# SCH-00001-AC-01.net
KiCad netlist of a schematic drawn in Altium Designer
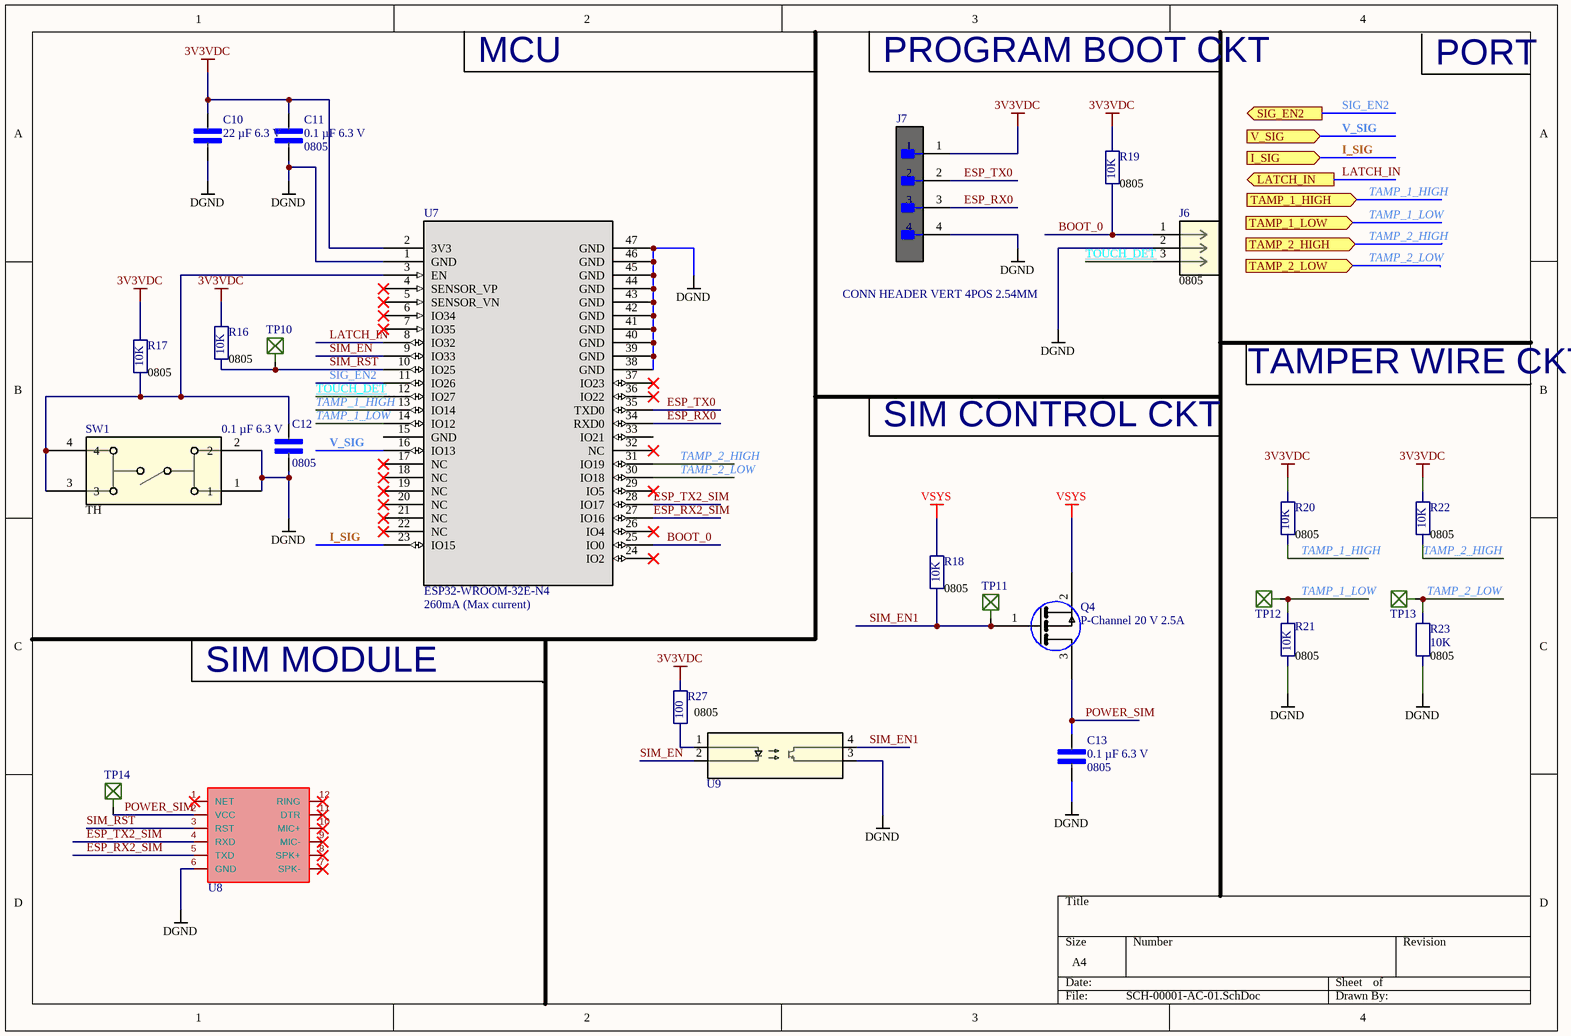
[diagram p0: SCH-00001-AC-01.SchDoc]

(export (version "E")
  (design (tool "Eeschema 10.0.6"))
  (components
    (comp (ref "C10")
      (value "22 µF 6.3 V")
      (footprint "CAP0805")
      (description "22 µF ±10% 6.3V Ceramic Capacitor X5R 0805 (2012 Metric)")
      (fields
        (field (name "MANUFACTURER") "Samsung Electro-Mechanics")
        (field (name "MANUFACTURER PART NO.") "CL21A226KQCLRNC")
        (field (name "DATE DRAWN") "03/9/2024")
        (field (name "DRAWN BY") "Varun Chakravarthy")
      )
      (libsource (lib "00001-A-01") (part "CL21A226KQCLRNC"))
    )
    (comp (ref "C11")
      (value "0.1 µF 6.3 V")
      (footprint "CAP0805")
      (description "0.1 µF ±10% 6.3V Ceramic Capacitor X5R 0805 (2012 Metric)")
      (fields
        (field (name "MANUFACTURER") "KYOCERA AVX")
        (field (name "MANUFACTURER PART NO.") "08056D104KAT2A")
        (field (name "VALUE 2") "0805")
        (field (name "DATE DRAWN") "04/07/24")
        (field (name "DRAWN BY") "Varun Chakravarthy")
      )
      (libsource (lib "00001-A-01") (part "08056D104KAT2A"))
    )
    (comp (ref "C12")
      (value "0.1 µF 6.3 V")
      (footprint "CAP0805")
      (description "0.1 µF ±10% 6.3V Ceramic Capacitor X5R 0805 (2012 Metric)")
      (fields
        (field (name "MANUFACTURER") "KYOCERA AVX")
        (field (name "MANUFACTURER PART NO.") "08056D104KAT2A")
        (field (name "VALUE 2") "0805")
        (field (name "DATE DRAWN") "04/07/24")
        (field (name "DRAWN BY") "Varun Chakravarthy")
      )
      (libsource (lib "00001-A-01") (part "08056D104KAT2A"))
    )
    (comp (ref "C13")
      (value "0.1 µF 6.3 V")
      (footprint "CAP0805")
      (description "0.1 µF ±10% 6.3V Ceramic Capacitor X5R 0805 (2012 Metric)")
      (fields
        (field (name "MANUFACTURER") "KYOCERA AVX")
        (field (name "MANUFACTURER PART NO.") "08056D104KAT2A")
        (field (name "VALUE 2") "0805")
        (field (name "DATE DRAWN") "04/07/24")
        (field (name "DRAWN BY") "Varun Chakravarthy")
      )
      (libsource (lib "00001-A-01") (part "08056D104KAT2A"))
    )
    (comp (ref "J6")
      (value "PRPC003SAAN-RC")
      (footprint "CONN_PRPC003SAAN-RC_SUL")
      (description "Connector Header Through Hole 3 position 0.100\" (2.54mm)")
      (fields
        (field (name "MANUFACTURER") "Sullins Connector Solutions")
        (field (name "DISTRIBUTOR 1 PART NO.") "S1011EC-03-ND")
        (field (name "PACKAGE") "0805")
        (field (name "DATE DRAWN") "12/9/2024")
        (field (name "VERIFIED BY") "*")
      )
      (libsource (lib "00001-A-01") (part "PRPC003SAAN-RC"))
    )
    (comp (ref "J7")
      (value "CONN HEADER VERT 4POS 2.54MM")
      (footprint "Amphenol_FCI_0_MFG")
      (description "Connector Header Through Hole 4 position 0.100\" (2.54mm)")
      (fields
        (field (name "MANUFACTURER") "Amphenol ICC (FCI)")
        (field (name "MANUFACTURER PART NO.") "68000-204HLF")
        (field (name "DATE DRAWN") "3/9/2024")
        (field (name "VERIFIED BY") "*")
      )
      (libsource (lib "00001-A-01") (part "68000-204HLF"))
    )
    (comp (ref "Q4")
      (value "P-Channel 20 V 2.5A")
      (footprint "SOT23_DMG2301U_DIO")
      (description "P-Channel 20 V 2.5A (Ta) 800mW (Ta) Surface Mount SOT-23-3")
      (fields
        (field (name "MANUFACTURER") "Diodes Incorporated")
        (field (name "MANUFACTURER PART NO.") "DMG2301U-7")
        (field (name "DATE DRAWN") "05/09/24")
        (field (name "DRAWN BY") "Varun Chakravarthy")
      )
      (libsource (lib "00001-A-01") (part "DMG2301U-7"))
    )
    (comp (ref "R16")
      (value "10K")
      (footprint "RES0805")
      (description "10 kOhms ±0.1% 0.125W, 1/8W Chip Resistor 0805 (2012 Metric) Automotive AEC-Q200 Thin Film")
      (fields
        (field (name "MANUFACTURER") "Panasonic Electronic Components")
        (field (name "MANUFACTURER PART NO.") "ERA-6AEB103V")
        (field (name "PACKAGE") "0805")
        (field (name "DATE DRAWN") "1/9/2024")
        (field (name "VERIFIED BY") "*")
      )
      (libsource (lib "00001-A-01") (part "ERA-6AEB103V"))
    )
    (comp (ref "R17")
      (value "10K")
      (footprint "RES0805")
      (description "10 kOhms ±0.1% 0.125W, 1/8W Chip Resistor 0805 (2012 Metric) Automotive AEC-Q200 Thin Film")
      (fields
        (field (name "MANUFACTURER") "Panasonic Electronic Components")
        (field (name "MANUFACTURER PART NO.") "ERA-6AEB103V")
        (field (name "PACKAGE") "0805")
        (field (name "DATE DRAWN") "1/9/2024")
        (field (name "VERIFIED BY") "*")
      )
      (libsource (lib "00001-A-01") (part "ERA-6AEB103V"))
    )
    (comp (ref "R18")
      (value "10K")
      (footprint "RES0805")
      (description "10 kOhms ±0.1% 0.125W, 1/8W Chip Resistor 0805 (2012 Metric) Automotive AEC-Q200 Thin Film")
      (fields
        (field (name "MANUFACTURER") "Panasonic Electronic Components")
        (field (name "MANUFACTURER PART NO.") "ERA-6AEB103V")
        (field (name "PACKAGE") "0805")
        (field (name "DATE DRAWN") "1/9/2024")
        (field (name "VERIFIED BY") "*")
      )
      (libsource (lib "00001-A-01") (part "ERA-6AEB103V"))
    )
    (comp (ref "R19")
      (value "10K")
      (footprint "RES0805")
      (description "10 kOhms ±0.1% 0.125W, 1/8W Chip Resistor 0805 (2012 Metric) Automotive AEC-Q200 Thin Film")
      (fields
        (field (name "MANUFACTURER") "Panasonic Electronic Components")
        (field (name "MANUFACTURER PART NO.") "ERA-6AEB103V")
        (field (name "PACKAGE") "0805")
        (field (name "DATE DRAWN") "1/9/2024")
        (field (name "VERIFIED BY") "*")
      )
      (libsource (lib "00001-A-01") (part "ERA-6AEB103V"))
    )
    (comp (ref "R20")
      (value "10K")
      (footprint "RES0805")
      (description "10 kOhms ±0.1% 0.125W, 1/8W Chip Resistor 0805 (2012 Metric) Automotive AEC-Q200 Thin Film")
      (fields
        (field (name "MANUFACTURER") "Panasonic Electronic Components")
        (field (name "MANUFACTURER PART NO.") "ERA-6AEB103V")
        (field (name "PACKAGE") "0805")
        (field (name "DATE DRAWN") "1/9/2024")
        (field (name "VERIFIED BY") "*")
      )
      (libsource (lib "00001-A-01") (part "ERA-6AEB103V"))
    )
    (comp (ref "R21")
      (value "10K")
      (footprint "RES0805")
      (description "10 kOhms ±0.1% 0.125W, 1/8W Chip Resistor 0805 (2012 Metric) Automotive AEC-Q200 Thin Film")
      (fields
        (field (name "MANUFACTURER") "Panasonic Electronic Components")
        (field (name "MANUFACTURER PART NO.") "ERA-6AEB103V")
        (field (name "PACKAGE") "0805")
        (field (name "DATE DRAWN") "1/9/2024")
        (field (name "VERIFIED BY") "*")
      )
      (libsource (lib "00001-A-01") (part "ERA-6AEB103V"))
    )
    (comp (ref "R22")
      (value "10K")
      (footprint "RES0805")
      (description "10 kOhms ±0.1% 0.125W, 1/8W Chip Resistor 0805 (2012 Metric) Automotive AEC-Q200 Thin Film")
      (fields
        (field (name "MANUFACTURER") "Panasonic Electronic Components")
        (field (name "MANUFACTURER PART NO.") "ERA-6AEB103V")
        (field (name "PACKAGE") "0805")
        (field (name "DATE DRAWN") "1/9/2024")
        (field (name "VERIFIED BY") "*")
      )
      (libsource (lib "00001-A-01") (part "ERA-6AEB103V"))
    )
    (comp (ref "R23")
      (value "10K")
      (footprint "RES0805")
      (description "10 kOhms ±0.1% 0.125W, 1/8W Chip Resistor 0805 (2012 Metric) Automotive AEC-Q200 Thin Film")
      (fields
        (field (name "MANUFACTURER") "Panasonic Electronic Components")
        (field (name "MANUFACTURER PART NO.") "ERA-6AEB103V")
        (field (name "PACKAGE") "0805")
        (field (name "DATE DRAWN") "1/9/2024")
        (field (name "VERIFIED BY") "*")
      )
      (libsource (lib "00001-A-01") (part "ERA-6AEB103V"))
    )
    (comp (ref "R27")
      (value "100")
      (footprint "RES0805")
      (description "100 Ohms ±5% 0.125W, 1/8W Chip Resistor 0805 (2012 Metric) Automotive AEC-Q200 Thick Film")
      (fields
        (field (name "MANUFACTURER") "Panasonic Electronic Components")
        (field (name "MANUFACTURER PART NO.") "ERJ-6GEYJ101V")
        (field (name "PACKAGE") "0805")
        (field (name "DATE DRAWN") "1/9/2024")
        (field (name "VERIFIED BY") "*")
      )
      (libsource (lib "00001-A-01") (part "ERJ-6GEYJ101V"))
    )
    (comp (ref "SW1")
      (value "1-1825910-8")
      (footprint "SW4_1825910-E_TEC")
      (description "Tactile Switch SPST-NO Top Actuated Through Hole")
      (fields
        (field (name "MANUFACTURER") "TE Connectivity ALCOSWITCH Switches")
        (field (name "DISTRIBUTOR 1 PART NO.") "450-1647-ND")
        (field (name "PACKAGE") "TH")
        (field (name "DATE DRAWN") "12/9/2024")
        (field (name "VERIFIED BY") "*")
      )
      (libsource (lib "00001-A-01") (part "1-1825910-8"))
    )
    (comp (ref "TP10")
      (value "TEST point")
      (footprint "TEST_POINT")
      (libsource (lib "00001-A-01") (part "TP"))
    )
    (comp (ref "TP11")
      (value "TEST point")
      (footprint "TEST_POINT")
      (libsource (lib "00001-A-01") (part "TP"))
    )
    (comp (ref "TP12")
      (value "TEST point")
      (footprint "TEST_POINT")
      (libsource (lib "00001-A-01") (part "TP"))
    )
    (comp (ref "TP13")
      (value "TEST point")
      (footprint "TEST_POINT")
      (libsource (lib "00001-A-01") (part "TP"))
    )
    (comp (ref "TP14")
      (value "TEST point")
      (footprint "TEST_POINT")
      (libsource (lib "00001-A-01") (part "TP"))
    )
    (comp (ref "U7")
      (value "ESP32-WROOM-32E-N4")
      (footprint "ESP32­WROOM­32E_EXP")
      (fields
        (field (name "MANUFACTURER") "Espressif Systems")
        (field (name "DISTRIBUTOR 1 PART NO.") "1965-ESP32-WROOM-32E-N4CT-ND")
        (field (name "MANUFACTURER PART NO.") "ESP32-WROOM-32E-N4")
        (field (name "VALUE1") "260mA (Max current)")
        (field (name "DRAWN BY") "Varun")
        (field (name "DATE DRAWN") "2/9/2024")
        (field (name "VERIFIED BY") "*")
      )
      (libsource (lib "00001-A-01") (part "ESP32-WROOM-32E-N4"))
    )
    (comp (ref "U8")
      (value "SIM800L")
      (footprint "SIM800L-CORE")
      (description "miniature cellular GSM modem")
      (fields
        (field (name "MANUFACTURER") "SIMCOM")
        (field (name "DATE DRAWN") "3/9/2024")
        (field (name "VERIFIED BY") "*")
      )
      (libsource (lib "00001-A-01") (part "SIM800L"))
    )
    (comp (ref "U9")
      (value "PC81710NIP1B")
      (footprint "SOP_PC8171_SCT-M")
      (description "Optoisolator Transistor Output 5000Vrms 1 Channel 4-SMD")
      (fields
        (field (name "MANUFACTURER") "SHARP/Socle Technology")
        (field (name "DISTRIBUTOR 1 PART NO.") "1855-1014-1-ND")
        (field (name "DATE DRAWN") "05/07/24")
        (field (name "VERIFIED BY") "*")
      )
      (libsource (lib "00001-A-01") (part "PC81710NIP1B"))
    )
  )
  (nets
    (net (code "1") (name "/BOOT_0") (class "Default")
      (node (ref "J6") (pin "1") (pinfunction "1_1") (pintype "passive"))
      (node (ref "R19") (pin "1") (pinfunction "1_1") (pintype "passive"))
      (node (ref "U7") (pin "25") (pinfunction "IO0_25") (pintype "bidirectional"))
    )
    (net (code "2") (name "/ESP_RX0") (class "Default")
      (node (ref "J7") (pin "3") (pinfunction "3_3") (pintype "passive"))
      (node (ref "U7") (pin "34") (pinfunction "RXD0_34") (pintype "bidirectional"))
    )
    (net (code "3") (name "/ESP_RX2_SIM") (class "Default")
      (node (ref "U7") (pin "27") (pinfunction "IO16_27") (pintype "bidirectional"))
      (node (ref "U8") (pin "5") (pinfunction "TXD_5") (pintype "passive"))
    )
    (net (code "4") (name "/ESP_TX0") (class "Default")
      (node (ref "J7") (pin "2") (pinfunction "2_2") (pintype "passive"))
      (node (ref "U7") (pin "35") (pinfunction "TXD0_35") (pintype "bidirectional"))
    )
    (net (code "5") (name "/ESP_TX2_SIM") (class "Default")
      (node (ref "U7") (pin "28") (pinfunction "IO17_28") (pintype "bidirectional"))
      (node (ref "U8") (pin "4") (pinfunction "RXD_4") (pintype "passive"))
    )
    (net (code "6") (name "/I_SIG") (class "Default")
      (node (ref "U7") (pin "23") (pinfunction "IO15_23") (pintype "bidirectional"))
    )
    (net (code "7") (name "/LATCH_IN") (class "Default")
      (node (ref "U7") (pin "8") (pinfunction "IO32_8") (pintype "bidirectional"))
    )
    (net (code "8") (name "/POWER_SIM") (class "Default")
      (node (ref "C13") (pin "1") (pinfunction "+_1") (pintype "passive"))
      (node (ref "Q4") (pin "3") (pinfunction "3/D_3") (pintype "passive"))
      (node (ref "TP14") (pin "1") (pinfunction "G_1") (pintype "passive"))
      (node (ref "U8") (pin "2") (pinfunction "VCC_2") (pintype "passive"))
    )
    (net (code "9") (name "/SIG_EN2") (class "Default")
      (node (ref "U7") (pin "11") (pinfunction "IO26_11") (pintype "bidirectional"))
    )
    (net (code "10") (name "/SIM_EN") (class "Default")
      (node (ref "U7") (pin "9") (pinfunction "IO33_9") (pintype "bidirectional"))
      (node (ref "U9") (pin "2") (pinfunction "CATHODE_2") (pintype "passive"))
    )
    (net (code "11") (name "/SIM_EN1") (class "Default")
      (node (ref "Q4") (pin "1") (pinfunction "1/G_1") (pintype "passive"))
      (node (ref "R18") (pin "1") (pinfunction "1_1") (pintype "passive"))
      (node (ref "TP11") (pin "1") (pinfunction "G_1") (pintype "passive"))
      (node (ref "U9") (pin "4") (pinfunction "COLLECTOR_4") (pintype "passive"))
    )
    (net (code "12") (name "/SIM_RST") (class "Default")
      (node (ref "R16") (pin "1") (pinfunction "1_1") (pintype "passive"))
      (node (ref "TP10") (pin "1") (pinfunction "G_1") (pintype "passive"))
      (node (ref "U7") (pin "10") (pinfunction "IO25_10") (pintype "bidirectional"))
      (node (ref "U8") (pin "3") (pinfunction "RST_3") (pintype "passive"))
    )
    (net (code "13") (name "/TAMP_1_HIGH") (class "Default")
      (node (ref "R20") (pin "1") (pinfunction "1_1") (pintype "passive"))
      (node (ref "U7") (pin "13") (pinfunction "IO14_13") (pintype "bidirectional"))
    )
    (net (code "14") (name "/TAMP_1_LOW") (class "Default")
      (node (ref "R21") (pin "2") (pinfunction "2_2") (pintype "passive"))
      (node (ref "TP12") (pin "1") (pinfunction "G_1") (pintype "passive"))
      (node (ref "U7") (pin "14") (pinfunction "IO12_14") (pintype "bidirectional"))
    )
    (net (code "15") (name "/TAMP_2_HIGH") (class "Default")
      (node (ref "R22") (pin "1") (pinfunction "1_1") (pintype "passive"))
      (node (ref "U7") (pin "31") (pinfunction "IO19_31") (pintype "bidirectional"))
    )
    (net (code "16") (name "/TAMP_2_LOW") (class "Default")
      (node (ref "R23") (pin "2") (pinfunction "2_2") (pintype "passive"))
      (node (ref "TP13") (pin "1") (pinfunction "G_1") (pintype "passive"))
      (node (ref "U7") (pin "30") (pinfunction "IO18_30") (pintype "bidirectional"))
    )
    (net (code "17") (name "/TOUCH_DET") (class "Default")
      (node (ref "J6") (pin "3") (pinfunction "3_3") (pintype "passive"))
      (node (ref "U7") (pin "12") (pinfunction "IO27_12") (pintype "bidirectional"))
    )
    (net (code "18") (name "/V_SIG") (class "Default")
      (node (ref "U7") (pin "16") (pinfunction "IO13_16") (pintype "bidirectional"))
    )
    (net (code "19") (name "3V3VDC") (class "Default")
      (node (ref "C10") (pin "1") (pinfunction "+_1") (pintype "passive"))
      (node (ref "C11") (pin "1") (pinfunction "+_1") (pintype "passive"))
      (node (ref "J7") (pin "1") (pinfunction "1_1") (pintype "passive"))
      (node (ref "R16") (pin "2") (pinfunction "2_2") (pintype "passive"))
      (node (ref "R17") (pin "2") (pinfunction "2_2") (pintype "passive"))
      (node (ref "R19") (pin "2") (pinfunction "2_2") (pintype "passive"))
      (node (ref "R20") (pin "2") (pinfunction "2_2") (pintype "passive"))
      (node (ref "R22") (pin "2") (pinfunction "2_2") (pintype "passive"))
      (node (ref "R27") (pin "2") (pinfunction "2_2") (pintype "passive"))
      (node (ref "U7") (pin "2") (pinfunction "3V3_2") (pintype "power_in"))
    )
    (net (code "20") (name "DGND") (class "Default")
      (node (ref "C10") (pin "2") (pinfunction "-_2") (pintype "passive"))
      (node (ref "C11") (pin "2") (pinfunction "-_2") (pintype "passive"))
      (node (ref "C12") (pin "2") (pinfunction "-_2") (pintype "passive"))
      (node (ref "C13") (pin "2") (pinfunction "-_2") (pintype "passive"))
      (node (ref "J6") (pin "2") (pinfunction "2_2") (pintype "passive"))
      (node (ref "J7") (pin "4") (pinfunction "4_4") (pintype "passive"))
      (node (ref "R21") (pin "1") (pinfunction "1_1") (pintype "passive"))
      (node (ref "R23") (pin "1") (pinfunction "1_1") (pintype "passive"))
      (node (ref "SW1") (pin "1") (pinfunction "1_1") (pintype "passive"))
      (node (ref "SW1") (pin "2") (pinfunction "2_2") (pintype "passive"))
      (node (ref "U7") (pin "1") (pinfunction "GND_1") (pintype "power_in"))
      (node (ref "U7") (pin "38") (pinfunction "GND_38") (pintype "power_in"))
      (node (ref "U7") (pin "39") (pinfunction "GND_39") (pintype "power_in"))
      (node (ref "U7") (pin "40") (pinfunction "GND_40") (pintype "power_in"))
      (node (ref "U7") (pin "41") (pinfunction "GND_41") (pintype "power_in"))
      (node (ref "U7") (pin "42") (pinfunction "GND_42") (pintype "power_in"))
      (node (ref "U7") (pin "43") (pinfunction "GND_43") (pintype "power_in"))
      (node (ref "U7") (pin "44") (pinfunction "GND_44") (pintype "power_in"))
      (node (ref "U7") (pin "45") (pinfunction "GND_45") (pintype "power_in"))
      (node (ref "U7") (pin "46") (pinfunction "GND_46") (pintype "power_in"))
      (node (ref "U7") (pin "47") (pinfunction "GND_47") (pintype "power_in"))
      (node (ref "U8") (pin "6") (pinfunction "GND_6") (pintype "passive"))
      (node (ref "U9") (pin "3") (pinfunction "EMITTER_3") (pintype "passive"))
    )
    (net (code "21") (name "Net-(C12-+)") (class "Default")
      (node (ref "C12") (pin "1") (pinfunction "+_1") (pintype "passive"))
      (node (ref "R17") (pin "1") (pinfunction "1_1") (pintype "passive"))
      (node (ref "SW1") (pin "3") (pinfunction "3_3") (pintype "passive"))
      (node (ref "SW1") (pin "4") (pinfunction "4_4") (pintype "passive"))
      (node (ref "U7") (pin "3") (pinfunction "EN_3") (pintype "input"))
    )
    (net (code "22") (name "Net-(U9-ANODE)") (class "Default")
      (node (ref "R27") (pin "1") (pinfunction "1_1") (pintype "passive"))
      (node (ref "U9") (pin "1") (pinfunction "ANODE_1") (pintype "passive"))
    )
    (net (code "23") (name "VSYS") (class "Default")
      (node (ref "Q4") (pin "2") (pinfunction "2/S_2") (pintype "passive"))
      (node (ref "R18") (pin "2") (pinfunction "2_2") (pintype "passive"))
    )
    (net (code "24") (name "unconnected-(U7-GND-Pad15)") (class "Default")
      (node (ref "U7") (pin "15") (pinfunction "GND_15") (pintype "power_in"))
    )
    (net (code "25") (name "unconnected-(U7-IO2-Pad24)") (class "Default")
      (node (ref "U7") (pin "24") (pinfunction "IO2_24") (pintype "bidirectional+no_connect"))
    )
    (net (code "26") (name "unconnected-(U7-IO4-Pad26)") (class "Default")
      (node (ref "U7") (pin "26") (pinfunction "IO4_26") (pintype "bidirectional+no_connect"))
    )
    (net (code "27") (name "unconnected-(U7-IO5-Pad29)") (class "Default")
      (node (ref "U7") (pin "29") (pinfunction "IO5_29") (pintype "bidirectional+no_connect"))
    )
    (net (code "28") (name "unconnected-(U7-IO21-Pad33)") (class "Default")
      (node (ref "U7") (pin "33") (pinfunction "IO21_33") (pintype "bidirectional"))
    )
    (net (code "29") (name "unconnected-(U7-IO22-Pad36)") (class "Default")
      (node (ref "U7") (pin "36") (pinfunction "IO22_36") (pintype "bidirectional+no_connect"))
    )
    (net (code "30") (name "unconnected-(U7-IO23-Pad37)") (class "Default")
      (node (ref "U7") (pin "37") (pinfunction "IO23_37") (pintype "bidirectional+no_connect"))
    )
    (net (code "31") (name "unconnected-(U7-IO34-Pad6)") (class "Default")
      (node (ref "U7") (pin "6") (pinfunction "IO34_6") (pintype "input+no_connect"))
    )
    (net (code "32") (name "unconnected-(U7-IO35-Pad7)") (class "Default")
      (node (ref "U7") (pin "7") (pinfunction "IO35_7") (pintype "input+no_connect"))
    )
    (net (code "33") (name "unconnected-(U7-NC-Pad17)") (class "Default")
      (node (ref "U7") (pin "17") (pinfunction "NC_17") (pintype "passive+no_connect"))
    )
    (net (code "34") (name "unconnected-(U7-NC-Pad18)") (class "Default")
      (node (ref "U7") (pin "18") (pinfunction "NC_18") (pintype "passive+no_connect"))
    )
    (net (code "35") (name "unconnected-(U7-NC-Pad19)") (class "Default")
      (node (ref "U7") (pin "19") (pinfunction "NC_19") (pintype "passive+no_connect"))
    )
    (net (code "36") (name "unconnected-(U7-NC-Pad20)") (class "Default")
      (node (ref "U7") (pin "20") (pinfunction "NC_20") (pintype "passive+no_connect"))
    )
    (net (code "37") (name "unconnected-(U7-NC-Pad21)") (class "Default")
      (node (ref "U7") (pin "21") (pinfunction "NC_21") (pintype "passive+no_connect"))
    )
    (net (code "38") (name "unconnected-(U7-NC-Pad22)") (class "Default")
      (node (ref "U7") (pin "22") (pinfunction "NC_22") (pintype "passive+no_connect"))
    )
    (net (code "39") (name "unconnected-(U7-NC-Pad32)") (class "Default")
      (node (ref "U7") (pin "32") (pinfunction "NC_32") (pintype "passive+no_connect"))
    )
    (net (code "40") (name "unconnected-(U7-SENSOR_VN-Pad5)") (class "Default")
      (node (ref "U7") (pin "5") (pinfunction "SENSOR_VN_5") (pintype "input+no_connect"))
    )
    (net (code "41") (name "unconnected-(U7-SENSOR_VP-Pad4)") (class "Default")
      (node (ref "U7") (pin "4") (pinfunction "SENSOR_VP_4") (pintype "input+no_connect"))
    )
    (net (code "42") (name "unconnected-(U8-DTR-Pad11)") (class "Default")
      (node (ref "U8") (pin "11") (pinfunction "DTR_11") (pintype "passive+no_connect"))
    )
    (net (code "43") (name "unconnected-(U8-MIC+-Pad10)") (class "Default")
      (node (ref "U8") (pin "10") (pinfunction "MIC+_10") (pintype "passive+no_connect"))
    )
    (net (code "44") (name "unconnected-(U8-MIC--Pad9)") (class "Default")
      (node (ref "U8") (pin "9") (pinfunction "MIC-_9") (pintype "passive+no_connect"))
    )
    (net (code "45") (name "unconnected-(U8-NET-Pad1)") (class "Default")
      (node (ref "U8") (pin "1") (pinfunction "NET_1") (pintype "passive+no_connect"))
    )
    (net (code "46") (name "unconnected-(U8-RING-Pad12)") (class "Default")
      (node (ref "U8") (pin "12") (pinfunction "RING_12") (pintype "passive+no_connect"))
    )
    (net (code "47") (name "unconnected-(U8-SPK+-Pad8)") (class "Default")
      (node (ref "U8") (pin "8") (pinfunction "SPK+_8") (pintype "passive+no_connect"))
    )
    (net (code "48") (name "unconnected-(U8-SPK--Pad7)") (class "Default")
      (node (ref "U8") (pin "7") (pinfunction "SPK-_7") (pintype "passive+no_connect"))
    )
  )
)
